# pyboard_arcobaleno.net
KiCad netlist of a schematic drawn in EAGLE
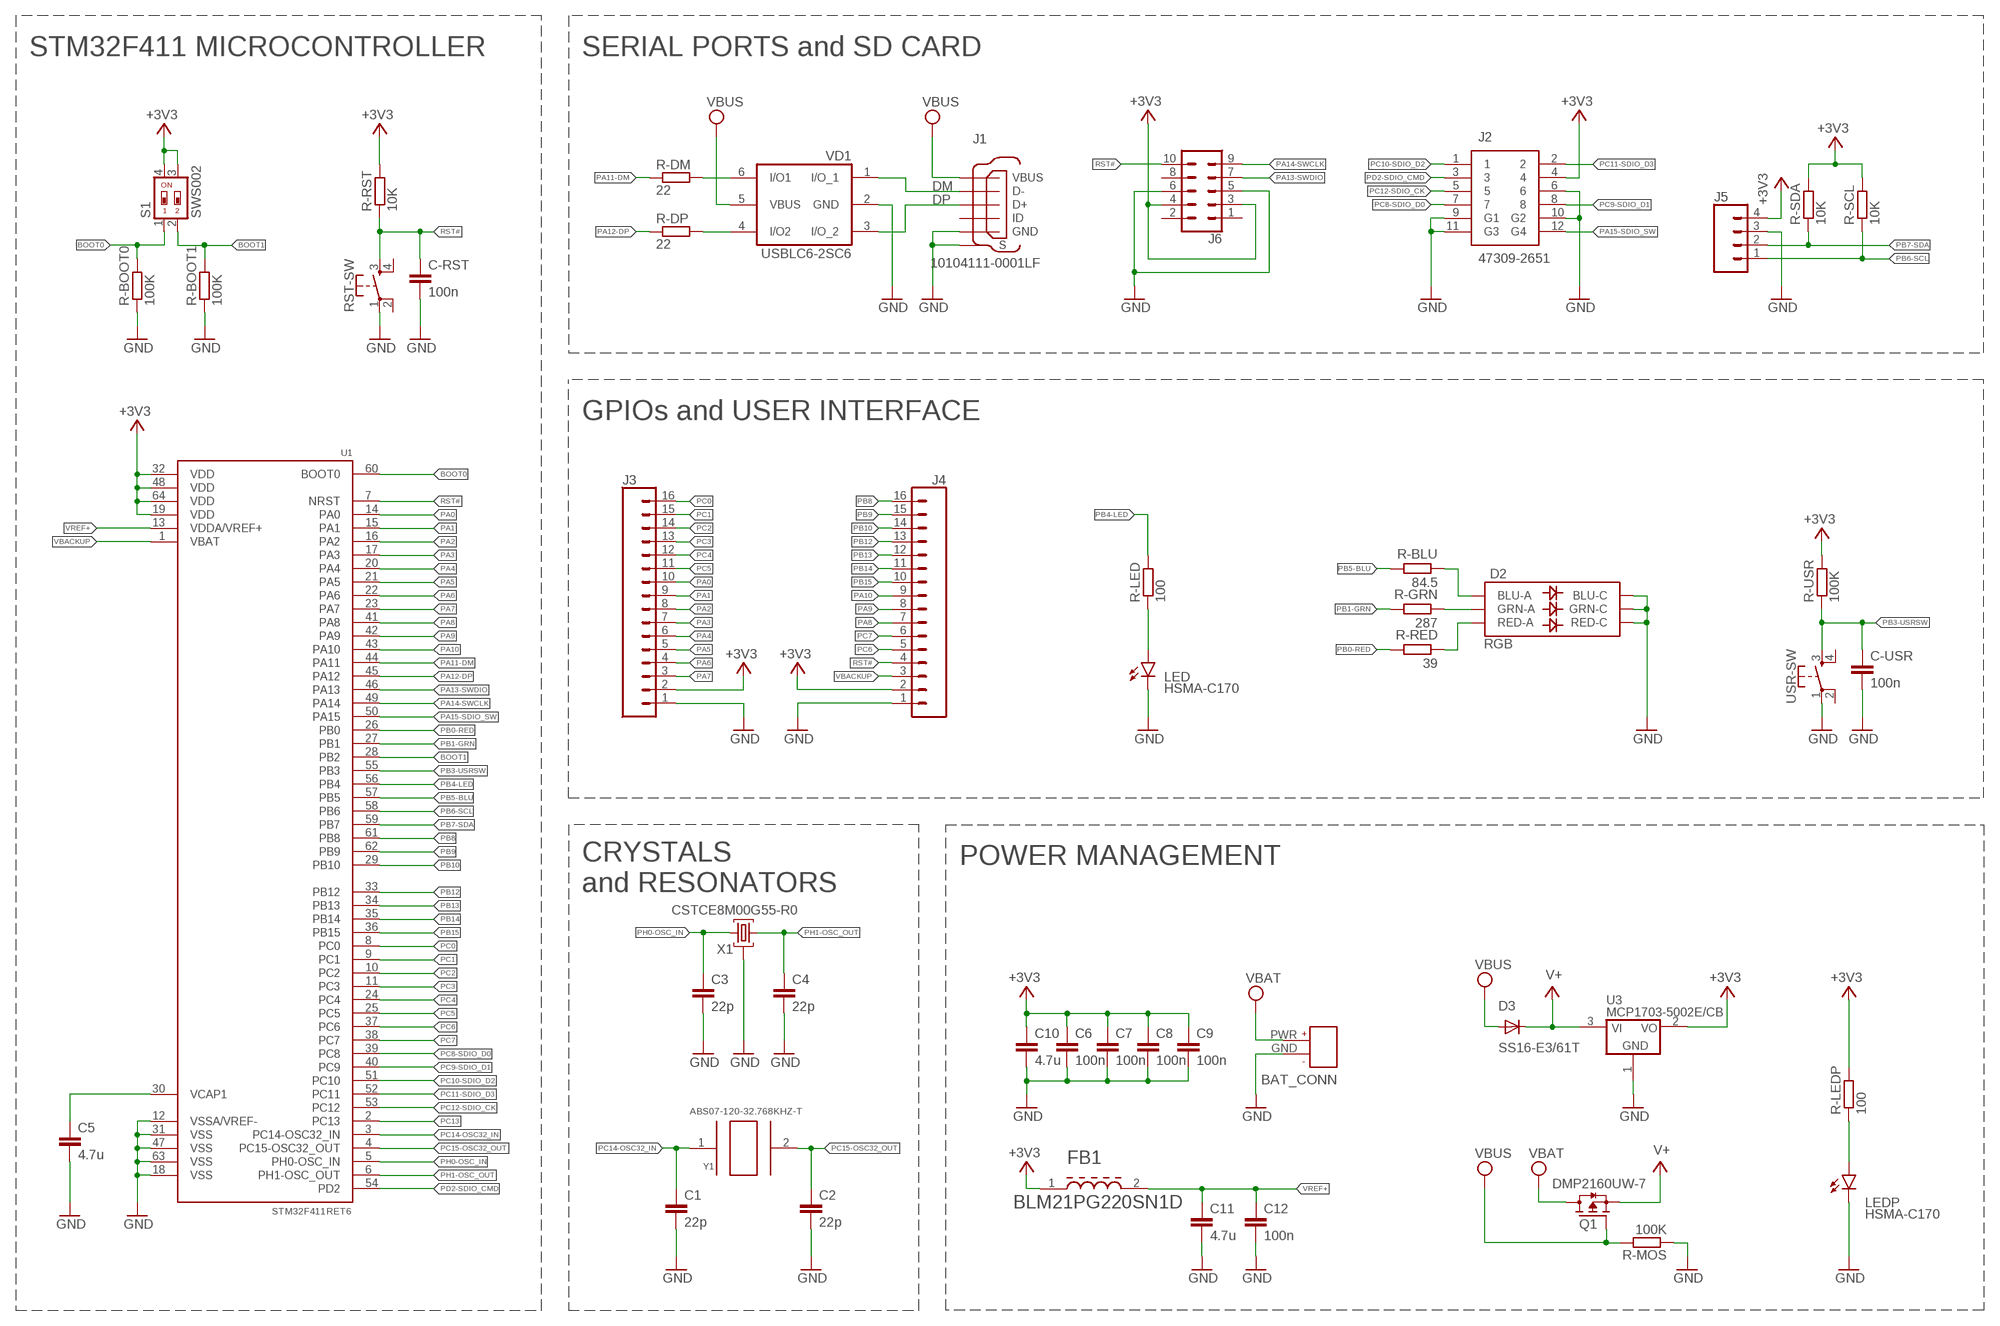
[diagram p0: schematic, sheet 1]

(export (version "E")
  (design (tool "Eeschema 10.0.6"))
  (components
    (comp (ref "BAT_CONN")
      (value "JST_PH_2PIN")
      (footprint "eagle-import:JST_PH_2PIN")
      (libsource (lib "eagle-import") (part "JST_PH_2PIN"))
    )
    (comp (ref "C-RST")
      (value "100n")
      (footprint "eagle-import:C0603")
      (libsource (lib "eagle-import") (part "C-EUC0603"))
    )
    (comp (ref "C-USR")
      (value "100n")
      (footprint "eagle-import:C0603")
      (libsource (lib "eagle-import") (part "C-EUC0603"))
    )
    (comp (ref "C1")
      (value "22p")
      (footprint "eagle-import:C0603")
      (libsource (lib "eagle-import") (part "C-EUC0603"))
    )
    (comp (ref "C2")
      (value "22p")
      (footprint "eagle-import:C0603")
      (libsource (lib "eagle-import") (part "C-EUC0603"))
    )
    (comp (ref "C3")
      (value "22p")
      (footprint "eagle-import:C0603")
      (libsource (lib "eagle-import") (part "C-EUC0603"))
    )
    (comp (ref "C4")
      (value "22p")
      (footprint "eagle-import:C0603")
      (libsource (lib "eagle-import") (part "C-EUC0603"))
    )
    (comp (ref "C5")
      (value "4.7u")
      (footprint "eagle-import:C1608")
      (libsource (lib "eagle-import") (part "rcl_334_C-EUC1608"))
    )
    (comp (ref "C6")
      (value "100n")
      (footprint "eagle-import:C0603")
      (libsource (lib "eagle-import") (part "C-EUC0603"))
    )
    (comp (ref "C7")
      (value "100n")
      (footprint "eagle-import:C0603")
      (libsource (lib "eagle-import") (part "C-EUC0603"))
    )
    (comp (ref "C8")
      (value "100n")
      (footprint "eagle-import:C0603")
      (libsource (lib "eagle-import") (part "C-EUC0603"))
    )
    (comp (ref "C9")
      (value "100n")
      (footprint "eagle-import:C0603")
      (libsource (lib "eagle-import") (part "C-EUC0603"))
    )
    (comp (ref "C10")
      (value "4.7u")
      (footprint "eagle-import:C1608")
      (libsource (lib "eagle-import") (part "rcl_334_C-EUC1608"))
    )
    (comp (ref "C11")
      (value "4.7u")
      (footprint "eagle-import:C1608")
      (libsource (lib "eagle-import") (part "rcl_334_C-EUC1608"))
    )
    (comp (ref "C12")
      (value "100n")
      (footprint "eagle-import:C0603")
      (libsource (lib "eagle-import") (part "C-EUC0603"))
    )
    (comp (ref "D2")
      (value "RGB")
      (footprint "eagle-import:PLCC-6-LED")
      (libsource (lib "eagle-import") (part "LED-RGBPLCC-6"))
    )
    (comp (ref "D3")
      (value "SS16-E3/61T")
      (footprint "eagle-import:DO214AA")
      (libsource (lib "eagle-import") (part "DIODE-DO214AA"))
    )
    (comp (ref "FB1")
      (value "MURATA_BLM21PG220SN1DMURATA_BLM21PG220SN1D_0_0")
      (footprint "eagle-import:MURATA_BLM21PG220SN1D_0")
      (fields (field (name "MF") "Murata") (field (name "MPN") "BLM21PG220SN1D"))
      (libsource (lib "eagle-import") (part "MURATA_BLM21PG220SN1DMURATA_BLM21PG220SN1D_0_0"))
    )
    (comp (ref "J1")
      (value "10104111-0001LF")
      (footprint "eagle-import:FRAMATOME_10104111-0001LF")
      (fields (field (name "MF") "Amphenol ICC"))
      (libsource (lib "eagle-import") (part "10104111-0001LF"))
    )
    (comp (ref "J2")
      (value "47309-2651")
      (footprint "eagle-import:47309-2651")
      (fields (field (name "MOUSER_PART_NUMBER") "538-47309-2651") (field (name "RS_PART_NUMBER") "7025485P"))
      (libsource (lib "eagle-import") (part "47309-2651"))
    )
    (comp (ref "J3")
      (value "CONN_16")
      (footprint "eagle-import:1X16")
      (libsource (lib "eagle-import") (part "CONN_16"))
    )
    (comp (ref "J4")
      (value "CONN_16")
      (footprint "eagle-import:1X16")
      (libsource (lib "eagle-import") (part "CONN_16"))
    )
    (comp (ref "J5")
      (value "CONN_04")
      (footprint "eagle-import:1X04")
      (libsource (lib "eagle-import") (part "CONN_04"))
    )
    (comp (ref "J6")
      (value "CONN_05X2PTH")
      (footprint "eagle-import:2X5")
      (libsource (lib "eagle-import") (part "CONN_05X2PTH"))
    )
    (comp (ref "LED")
      (value "HSMA-C170")
      (footprint "eagle-import:CHIPLED_0805")
      (libsource (lib "eagle-import") (part "LEDCHIPLED_0805"))
    )
    (comp (ref "LEDP")
      (value "HSMA-C170")
      (footprint "eagle-import:CHIPLED_0805")
      (libsource (lib "eagle-import") (part "LEDCHIPLED_0805"))
    )
    (comp (ref "Q1")
      (value "DMP2160UW-7")
      (footprint "eagle-import:SOT65P210X110-3N")
      (fields (field (name "DIGI-KEY_PART_NUMBER") "DMP2160UWDICT-ND") (field (name "MF") "Diodes Inc."))
      (libsource (lib "eagle-import") (part "DMP2160UW-7"))
    )
    (comp (ref "R-BLU")
      (value "84.5")
      (footprint "eagle-import:R0603")
      (libsource (lib "eagle-import") (part "R-EU_R0603"))
    )
    (comp (ref "R-BOOT0")
      (value "100K")
      (footprint "eagle-import:R0603")
      (libsource (lib "eagle-import") (part "R-EU_R0603"))
    )
    (comp (ref "R-BOOT1")
      (value "100K")
      (footprint "eagle-import:R0603")
      (libsource (lib "eagle-import") (part "R-EU_R0603"))
    )
    (comp (ref "R-DM")
      (value "22")
      (footprint "eagle-import:R0603")
      (libsource (lib "eagle-import") (part "R-EU_R0603"))
    )
    (comp (ref "R-DP")
      (value "22")
      (footprint "eagle-import:R0603")
      (libsource (lib "eagle-import") (part "R-EU_R0603"))
    )
    (comp (ref "R-GRN")
      (value "287")
      (footprint "eagle-import:R0603")
      (libsource (lib "eagle-import") (part "R-EU_R0603"))
    )
    (comp (ref "R-LED")
      (value "100")
      (footprint "eagle-import:R0603")
      (libsource (lib "eagle-import") (part "R-EU_R0603"))
    )
    (comp (ref "R-LEDP")
      (value "100")
      (footprint "eagle-import:R0603")
      (libsource (lib "eagle-import") (part "R-EU_R0603"))
    )
    (comp (ref "R-MOS")
      (value "100K")
      (footprint "eagle-import:R0603")
      (libsource (lib "eagle-import") (part "R-EU_R0603"))
    )
    (comp (ref "R-RED")
      (value "39")
      (footprint "eagle-import:R0603")
      (libsource (lib "eagle-import") (part "R-EU_R0603"))
    )
    (comp (ref "R-RST")
      (value "10K")
      (footprint "eagle-import:R0603")
      (libsource (lib "eagle-import") (part "R-EU_R0603"))
    )
    (comp (ref "R-SCL")
      (value "10K")
      (footprint "eagle-import:R0603")
      (libsource (lib "eagle-import") (part "R-EU_R0603"))
    )
    (comp (ref "R-SDA")
      (value "10K")
      (footprint "eagle-import:R0603")
      (libsource (lib "eagle-import") (part "R-EU_R0603"))
    )
    (comp (ref "R-USR")
      (value "100K")
      (footprint "eagle-import:R0603")
      (libsource (lib "eagle-import") (part "R-EU_R0603"))
    )
    (comp (ref "RST-SW")
      (value "MOMENTARY-SWITCH-SPST-2-SMD-5.2MM")
      (footprint "eagle-import:TACTILE_SWITCH_SMD_5.2MM")
      (libsource (lib "eagle-import") (part "MOMENTARY-SWITCH-SPST-2-SMD-5.2MM"))
    )
    (comp (ref "S1")
      (value "SWS002")
      (footprint "eagle-import:SMS-002")
      (libsource (lib "eagle-import") (part "SWS002"))
    )
    (comp (ref "U1")
      (value "STM32F411RET6")
      (footprint "eagle-import:QFP50P1200X1200X160-64N")
      (fields (field (name "MF") "STMicroelectronics"))
      (libsource (lib "eagle-import") (part "STM32F411RET6"))
    )
    (comp (ref "U3")
      (value "MCP1703-5002E/CB")
      (footprint "eagle-import:SOT23A_MICROCHIP_CB")
      (libsource (lib "eagle-import") (part "MCP170302E/CB-50"))
    )
    (comp (ref "USR-SW")
      (value "MOMENTARY-SWITCH-SPST-2-SMD-5.2MM")
      (footprint "eagle-import:TACTILE_SWITCH_SMD_5.2MM")
      (libsource (lib "eagle-import") (part "MOMENTARY-SWITCH-SPST-2-SMD-5.2MM"))
    )
    (comp (ref "VD1")
      (value "USBLC6-2SC6")
      (footprint "eagle-import:SOT-23-6L")
      (libsource (lib "eagle-import") (part "USBLC6-2SC6"))
    )
    (comp (ref "X1")
      (value "CSTCE8M00G55-R0")
      (footprint "eagle-import:CSTCE8M00G55-R0")
      (fields
        (field (name "DIGIKEY_PART_NUMBER") "490-1195-2-ND")
        (field (name "MANUFACTURER") "Murata Electronics North America")
        (field (name "CREATED_BY") "PCBLayout.com")
      )
      (libsource (lib "eagle-import") (part "CSTCE8M00G55-R0"))
    )
    (comp (ref "Y1")
      (value "ABS07-120-32.768KHZ-T")
      (footprint "eagle-import:XTAL_ABS07-120-32.768KHZ-T")
      (fields (field (name "DIGI-KEY_PART_NUMBER") "535-11937-1-ND") (field (name "MF") "Abracon"))
      (libsource (lib "eagle-import") (part "ABS07-120-32.768KHZ-T"))
    )
  )
  (nets
    (net (code "1") (name "+3V3") (class "Default")
      (node (ref "C10") (pin "1") (pinfunction "1_1") (pintype "passive"))
      (node (ref "C6") (pin "1") (pinfunction "1_1") (pintype "passive"))
      (node (ref "C7") (pin "1") (pinfunction "1_1") (pintype "passive"))
      (node (ref "C8") (pin "1") (pinfunction "1_1") (pintype "passive"))
      (node (ref "C9") (pin "1") (pinfunction "1_1") (pintype "passive"))
      (node (ref "FB1") (pin "1") (pinfunction "1_1") (pintype "passive"))
      (node (ref "J2") (pin "4") (pinfunction "4_4") (pintype "bidirectional"))
      (node (ref "J3") (pin "2") (pinfunction "2_2") (pintype "passive"))
      (node (ref "J4") (pin "2") (pinfunction "2_2") (pintype "passive"))
      (node (ref "J5") (pin "4") (pinfunction "4_4") (pintype "passive"))
      (node (ref "J6") (pin "3") (pinfunction "3_3") (pintype "passive"))
      (node (ref "J6") (pin "4") (pinfunction "4_4") (pintype "passive"))
      (node (ref "R-LEDP") (pin "2") (pinfunction "2_2") (pintype "passive"))
      (node (ref "R-RST") (pin "2") (pinfunction "2_2") (pintype "passive"))
      (node (ref "R-SCL") (pin "2") (pinfunction "2_2") (pintype "passive"))
      (node (ref "R-SDA") (pin "2") (pinfunction "2_2") (pintype "passive"))
      (node (ref "R-USR") (pin "2") (pinfunction "2_2") (pintype "passive"))
      (node (ref "S1") (pin "3") (pinfunction "3_3") (pintype "passive"))
      (node (ref "S1") (pin "4") (pinfunction "4_4") (pintype "passive"))
      (node (ref "U1") (pin "19") (pinfunction "VDD_19") (pintype "power_in"))
      (node (ref "U1") (pin "32") (pinfunction "VDD_32") (pintype "power_in"))
      (node (ref "U1") (pin "48") (pinfunction "VDD_48") (pintype "power_in"))
      (node (ref "U1") (pin "64") (pinfunction "VDD_64") (pintype "power_in"))
      (node (ref "U3") (pin "2") (pinfunction "VO_2") (pintype "passive"))
    )
    (net (code "2") (name "/DM") (class "Default")
      (node (ref "J1") (pin "2") (pinfunction "D-_2") (pintype "passive"))
      (node (ref "VD1") (pin "1") (pinfunction "I/O_1_1") (pintype "bidirectional"))
    )
    (net (code "3") (name "/DP") (class "Default")
      (node (ref "J1") (pin "3") (pinfunction "D+_3") (pintype "passive"))
      (node (ref "VD1") (pin "3") (pinfunction "I/O_2_3") (pintype "bidirectional"))
    )
    (net (code "4") (name "BOOT0") (class "Default")
      (node (ref "R-BOOT0") (pin "2") (pinfunction "2_2") (pintype "passive"))
      (node (ref "S1") (pin "1") (pinfunction "1_1") (pintype "passive"))
      (node (ref "U1") (pin "60") (pinfunction "BOOT0_60") (pintype "input"))
    )
    (net (code "5") (name "BOOT1") (class "Default")
      (node (ref "R-BOOT1") (pin "2") (pinfunction "2_2") (pintype "passive"))
      (node (ref "S1") (pin "2") (pinfunction "2_2") (pintype "passive"))
      (node (ref "U1") (pin "28") (pinfunction "PB2_28") (pintype "bidirectional"))
    )
    (net (code "6") (name "GND") (class "Default")
      (node (ref "BAT_CONN") (pin "GND") (pinfunction "GND_GND") (pintype "power_in"))
      (node (ref "C-RST") (pin "2") (pinfunction "2_2") (pintype "passive"))
      (node (ref "C-USR") (pin "2") (pinfunction "2_2") (pintype "passive"))
      (node (ref "C1") (pin "2") (pinfunction "2_2") (pintype "passive"))
      (node (ref "C10") (pin "2") (pinfunction "2_2") (pintype "passive"))
      (node (ref "C11") (pin "2") (pinfunction "2_2") (pintype "passive"))
      (node (ref "C12") (pin "2") (pinfunction "2_2") (pintype "passive"))
      (node (ref "C2") (pin "2") (pinfunction "2_2") (pintype "passive"))
      (node (ref "C3") (pin "2") (pinfunction "2_2") (pintype "passive"))
      (node (ref "C4") (pin "2") (pinfunction "2_2") (pintype "passive"))
      (node (ref "C5") (pin "2") (pinfunction "2_2") (pintype "passive"))
      (node (ref "C6") (pin "2") (pinfunction "2_2") (pintype "passive"))
      (node (ref "C7") (pin "2") (pinfunction "2_2") (pintype "passive"))
      (node (ref "C8") (pin "2") (pinfunction "2_2") (pintype "passive"))
      (node (ref "C9") (pin "2") (pinfunction "2_2") (pintype "passive"))
      (node (ref "D2") (pin "CB") (pinfunction "BLU-C_CB") (pintype "bidirectional"))
      (node (ref "D2") (pin "CG") (pinfunction "GRN-C_CG") (pintype "bidirectional"))
      (node (ref "D2") (pin "CR") (pinfunction "RED-C_CR") (pintype "bidirectional"))
      (node (ref "J1") (pin "5") (pinfunction "GND_5") (pintype "power_in"))
      (node (ref "J1") (pin "6") (pinfunction "S_6") (pintype "power_in"))
      (node (ref "J1") (pin "7") (pinfunction "S_7") (pintype "power_in"))
      (node (ref "J1") (pin "8") (pinfunction "S_8") (pintype "power_in"))
      (node (ref "J1") (pin "9") (pinfunction "S_9") (pintype "power_in"))
      (node (ref "J2") (pin "10") (pinfunction "G2_10") (pintype "bidirectional"))
      (node (ref "J2") (pin "11") (pinfunction "G3_11") (pintype "bidirectional"))
      (node (ref "J2") (pin "6") (pinfunction "6_6") (pintype "bidirectional"))
      (node (ref "J2") (pin "9") (pinfunction "G1_9") (pintype "bidirectional"))
      (node (ref "J3") (pin "1") (pinfunction "1_1") (pintype "passive"))
      (node (ref "J4") (pin "1") (pinfunction "1_1") (pintype "passive"))
      (node (ref "J5") (pin "3") (pinfunction "3_3") (pintype "passive"))
      (node (ref "J6") (pin "5") (pinfunction "5_5") (pintype "passive"))
      (node (ref "J6") (pin "6") (pinfunction "6_6") (pintype "passive"))
      (node (ref "LED") (pin "C") (pinfunction "C_C") (pintype "passive"))
      (node (ref "LEDP") (pin "C") (pinfunction "C_C") (pintype "passive"))
      (node (ref "R-BOOT0") (pin "1") (pinfunction "1_1") (pintype "passive"))
      (node (ref "R-BOOT1") (pin "1") (pinfunction "1_1") (pintype "passive"))
      (node (ref "R-MOS") (pin "1") (pinfunction "1_1") (pintype "passive"))
      (node (ref "RST-SW") (pin "1") (pinfunction "1_1") (pintype "passive"))
      (node (ref "U1") (pin "12") (pinfunction "VSSA/VREF-_12") (pintype "power_in"))
      (node (ref "U1") (pin "18") (pinfunction "VSS_18") (pintype "power_in"))
      (node (ref "U1") (pin "31") (pinfunction "VSS_31") (pintype "power_in"))
      (node (ref "U1") (pin "47") (pinfunction "VSS_47") (pintype "power_in"))
      (node (ref "U1") (pin "63") (pinfunction "VSS_63") (pintype "power_in"))
      (node (ref "U3") (pin "1") (pinfunction "GND_1") (pintype "power_in"))
      (node (ref "USR-SW") (pin "1") (pinfunction "1_1") (pintype "passive"))
      (node (ref "VD1") (pin "2") (pinfunction "GND_2") (pintype "bidirectional"))
      (node (ref "X1") (pin "2") (pinfunction "GND_2") (pintype "passive"))
    )
    (net (code "7") (name "Net-(D2-BLU-A)") (class "Default")
      (node (ref "D2") (pin "AB") (pinfunction "BLU-A_AB") (pintype "bidirectional"))
      (node (ref "R-BLU") (pin "1") (pinfunction "1_1") (pintype "passive"))
    )
    (net (code "8") (name "Net-(D2-GRN-A)") (class "Default")
      (node (ref "D2") (pin "AG") (pinfunction "GRN-A_AG") (pintype "bidirectional"))
      (node (ref "R-GRN") (pin "1") (pinfunction "1_1") (pintype "passive"))
    )
    (net (code "9") (name "Net-(D2-RED-A)") (class "Default")
      (node (ref "D2") (pin "AR") (pinfunction "RED-A_AR") (pintype "bidirectional"))
      (node (ref "R-RED") (pin "1") (pinfunction "1_1") (pintype "passive"))
    )
    (net (code "10") (name "Net-(LED-PadA)") (class "Default")
      (node (ref "LED") (pin "A") (pinfunction "A_A") (pintype "passive"))
      (node (ref "R-LED") (pin "1") (pinfunction "1_1") (pintype "passive"))
    )
    (net (code "11") (name "Net-(LEDP-PadA)") (class "Default")
      (node (ref "LEDP") (pin "A") (pinfunction "A_A") (pintype "passive"))
      (node (ref "R-LEDP") (pin "1") (pinfunction "1_1") (pintype "passive"))
    )
    (net (code "12") (name "Net-(U1-VCAP1)") (class "Default")
      (node (ref "C5") (pin "1") (pinfunction "1_1") (pintype "passive"))
      (node (ref "U1") (pin "30") (pinfunction "VCAP1_30") (pintype "passive"))
    )
    (net (code "13") (name "Net-(VD1-I{slash}O1)") (class "Default")
      (node (ref "R-DM") (pin "2") (pinfunction "2_2") (pintype "passive"))
      (node (ref "VD1") (pin "6") (pinfunction "I/O1_6") (pintype "bidirectional"))
    )
    (net (code "14") (name "Net-(VD1-I{slash}O2)") (class "Default")
      (node (ref "R-DP") (pin "2") (pinfunction "2_2") (pintype "passive"))
      (node (ref "VD1") (pin "4") (pinfunction "I/O2_4") (pintype "bidirectional"))
    )
    (net (code "15") (name "PA0") (class "Default")
      (node (ref "J3") (pin "10") (pinfunction "10_10") (pintype "passive"))
      (node (ref "U1") (pin "14") (pinfunction "PA0_14") (pintype "bidirectional"))
    )
    (net (code "16") (name "PA1") (class "Default")
      (node (ref "J3") (pin "9") (pinfunction "9_9") (pintype "passive"))
      (node (ref "U1") (pin "15") (pinfunction "PA1_15") (pintype "bidirectional"))
    )
    (net (code "17") (name "PA2") (class "Default")
      (node (ref "J3") (pin "8") (pinfunction "8_8") (pintype "passive"))
      (node (ref "U1") (pin "16") (pinfunction "PA2_16") (pintype "bidirectional"))
    )
    (net (code "18") (name "PA3") (class "Default")
      (node (ref "J3") (pin "7") (pinfunction "7_7") (pintype "passive"))
      (node (ref "U1") (pin "17") (pinfunction "PA3_17") (pintype "bidirectional"))
    )
    (net (code "19") (name "PA4") (class "Default")
      (node (ref "J3") (pin "6") (pinfunction "6_6") (pintype "passive"))
      (node (ref "U1") (pin "20") (pinfunction "PA4_20") (pintype "bidirectional"))
    )
    (net (code "20") (name "PA5") (class "Default")
      (node (ref "J3") (pin "5") (pinfunction "5_5") (pintype "passive"))
      (node (ref "U1") (pin "21") (pinfunction "PA5_21") (pintype "bidirectional"))
    )
    (net (code "21") (name "PA6") (class "Default")
      (node (ref "J3") (pin "4") (pinfunction "4_4") (pintype "passive"))
      (node (ref "U1") (pin "22") (pinfunction "PA6_22") (pintype "bidirectional"))
    )
    (net (code "22") (name "PA7") (class "Default")
      (node (ref "J3") (pin "3") (pinfunction "3_3") (pintype "passive"))
      (node (ref "U1") (pin "23") (pinfunction "PA7_23") (pintype "bidirectional"))
    )
    (net (code "23") (name "PA8") (class "Default")
      (node (ref "J4") (pin "7") (pinfunction "7_7") (pintype "passive"))
      (node (ref "U1") (pin "41") (pinfunction "PA8_41") (pintype "bidirectional"))
    )
    (net (code "24") (name "PA9") (class "Default")
      (node (ref "J4") (pin "8") (pinfunction "8_8") (pintype "passive"))
      (node (ref "U1") (pin "42") (pinfunction "PA9_42") (pintype "bidirectional"))
    )
    (net (code "25") (name "PA10") (class "Default")
      (node (ref "J4") (pin "9") (pinfunction "9_9") (pintype "passive"))
      (node (ref "U1") (pin "43") (pinfunction "PA10_43") (pintype "bidirectional"))
    )
    (net (code "26") (name "PA11-DM") (class "Default")
      (node (ref "R-DM") (pin "1") (pinfunction "1_1") (pintype "passive"))
      (node (ref "U1") (pin "44") (pinfunction "PA11_44") (pintype "bidirectional"))
    )
    (net (code "27") (name "PA12-DP") (class "Default")
      (node (ref "R-DP") (pin "1") (pinfunction "1_1") (pintype "passive"))
      (node (ref "U1") (pin "45") (pinfunction "PA12_45") (pintype "bidirectional"))
    )
    (net (code "28") (name "PA13-SWDIO") (class "Default")
      (node (ref "J6") (pin "7") (pinfunction "7_7") (pintype "passive"))
      (node (ref "U1") (pin "46") (pinfunction "PA13_46") (pintype "bidirectional"))
    )
    (net (code "29") (name "PA14-SWCLK") (class "Default")
      (node (ref "J6") (pin "9") (pinfunction "9_9") (pintype "passive"))
      (node (ref "U1") (pin "49") (pinfunction "PA14_49") (pintype "bidirectional"))
    )
    (net (code "30") (name "PA15-SDIO_SW") (class "Default")
      (node (ref "J2") (pin "12") (pinfunction "G4_12") (pintype "bidirectional"))
      (node (ref "U1") (pin "50") (pinfunction "PA15_50") (pintype "bidirectional"))
    )
    (net (code "31") (name "PB0-RED") (class "Default")
      (node (ref "R-RED") (pin "2") (pinfunction "2_2") (pintype "passive"))
      (node (ref "U1") (pin "26") (pinfunction "PB0_26") (pintype "bidirectional"))
    )
    (net (code "32") (name "PB1-GRN") (class "Default")
      (node (ref "R-GRN") (pin "2") (pinfunction "2_2") (pintype "passive"))
      (node (ref "U1") (pin "27") (pinfunction "PB1_27") (pintype "bidirectional"))
    )
    (net (code "33") (name "PB3-USRSW") (class "Default")
      (node (ref "C-USR") (pin "1") (pinfunction "1_1") (pintype "passive"))
      (node (ref "R-USR") (pin "1") (pinfunction "1_1") (pintype "passive"))
      (node (ref "U1") (pin "55") (pinfunction "PB3_55") (pintype "bidirectional"))
      (node (ref "USR-SW") (pin "3") (pinfunction "3_3") (pintype "passive"))
    )
    (net (code "34") (name "PB4-LED") (class "Default")
      (node (ref "R-LED") (pin "2") (pinfunction "2_2") (pintype "passive"))
      (node (ref "U1") (pin "56") (pinfunction "PB4_56") (pintype "bidirectional"))
    )
    (net (code "35") (name "PB5-BLU") (class "Default")
      (node (ref "R-BLU") (pin "2") (pinfunction "2_2") (pintype "passive"))
      (node (ref "U1") (pin "57") (pinfunction "PB5_57") (pintype "bidirectional"))
    )
    (net (code "36") (name "PB6-SCL") (class "Default")
      (node (ref "J5") (pin "1") (pinfunction "1_1") (pintype "passive"))
      (node (ref "R-SCL") (pin "1") (pinfunction "1_1") (pintype "passive"))
      (node (ref "U1") (pin "58") (pinfunction "PB6_58") (pintype "bidirectional"))
    )
    (net (code "37") (name "PB7-SDA") (class "Default")
      (node (ref "J5") (pin "2") (pinfunction "2_2") (pintype "passive"))
      (node (ref "R-SDA") (pin "1") (pinfunction "1_1") (pintype "passive"))
      (node (ref "U1") (pin "59") (pinfunction "PB7_59") (pintype "bidirectional"))
    )
    (net (code "38") (name "PB8") (class "Default")
      (node (ref "J4") (pin "16") (pinfunction "16_16") (pintype "passive"))
      (node (ref "U1") (pin "61") (pinfunction "PB8_61") (pintype "bidirectional"))
    )
    (net (code "39") (name "PB9") (class "Default")
      (node (ref "J4") (pin "15") (pinfunction "15_15") (pintype "passive"))
      (node (ref "U1") (pin "62") (pinfunction "PB9_62") (pintype "bidirectional"))
    )
    (net (code "40") (name "PB10") (class "Default")
      (node (ref "J4") (pin "14") (pinfunction "14_14") (pintype "passive"))
      (node (ref "U1") (pin "29") (pinfunction "PB10_29") (pintype "bidirectional"))
    )
    (net (code "41") (name "PB12") (class "Default")
      (node (ref "J4") (pin "13") (pinfunction "13_13") (pintype "passive"))
      (node (ref "U1") (pin "33") (pinfunction "PB12_33") (pintype "bidirectional"))
    )
    (net (code "42") (name "PB13") (class "Default")
      (node (ref "J4") (pin "12") (pinfunction "12_12") (pintype "passive"))
      (node (ref "U1") (pin "34") (pinfunction "PB13_34") (pintype "bidirectional"))
    )
    (net (code "43") (name "PB14") (class "Default")
      (node (ref "J4") (pin "11") (pinfunction "11_11") (pintype "passive"))
      (node (ref "U1") (pin "35") (pinfunction "PB14_35") (pintype "bidirectional"))
    )
    (net (code "44") (name "PB15") (class "Default")
      (node (ref "J4") (pin "10") (pinfunction "10_10") (pintype "passive"))
      (node (ref "U1") (pin "36") (pinfunction "PB15_36") (pintype "bidirectional"))
    )
    (net (code "45") (name "PC0") (class "Default")
      (node (ref "J3") (pin "16") (pinfunction "16_16") (pintype "passive"))
      (node (ref "U1") (pin "8") (pinfunction "PC0_8") (pintype "bidirectional"))
    )
    (net (code "46") (name "PC1") (class "Default")
      (node (ref "J3") (pin "15") (pinfunction "15_15") (pintype "passive"))
      (node (ref "U1") (pin "9") (pinfunction "PC1_9") (pintype "bidirectional"))
    )
    (net (code "47") (name "PC2") (class "Default")
      (node (ref "J3") (pin "14") (pinfunction "14_14") (pintype "passive"))
      (node (ref "U1") (pin "10") (pinfunction "PC2_10") (pintype "bidirectional"))
    )
    (net (code "48") (name "PC3") (class "Default")
      (node (ref "J3") (pin "13") (pinfunction "13_13") (pintype "passive"))
      (node (ref "U1") (pin "11") (pinfunction "PC3_11") (pintype "bidirectional"))
    )
    (net (code "49") (name "PC4") (class "Default")
      (node (ref "J3") (pin "12") (pinfunction "12_12") (pintype "passive"))
      (node (ref "U1") (pin "24") (pinfunction "PC4_24") (pintype "bidirectional"))
    )
    (net (code "50") (name "PC5") (class "Default")
      (node (ref "J3") (pin "11") (pinfunction "11_11") (pintype "passive"))
      (node (ref "U1") (pin "25") (pinfunction "PC5_25") (pintype "bidirectional"))
    )
    (net (code "51") (name "PC6") (class "Default")
      (node (ref "J4") (pin "5") (pinfunction "5_5") (pintype "passive"))
      (node (ref "U1") (pin "37") (pinfunction "PC6_37") (pintype "bidirectional"))
    )
    (net (code "52") (name "PC7") (class "Default")
      (node (ref "J4") (pin "6") (pinfunction "6_6") (pintype "passive"))
      (node (ref "U1") (pin "38") (pinfunction "PC7_38") (pintype "bidirectional"))
    )
    (net (code "53") (name "PC8-SDIO_D0") (class "Default")
      (node (ref "J2") (pin "7") (pinfunction "7_7") (pintype "bidirectional"))
      (node (ref "U1") (pin "39") (pinfunction "PC8_39") (pintype "bidirectional"))
    )
    (net (code "54") (name "PC9-SDIO_D1") (class "Default")
      (node (ref "J2") (pin "8") (pinfunction "8_8") (pintype "bidirectional"))
      (node (ref "U1") (pin "40") (pinfunction "PC9_40") (pintype "bidirectional"))
    )
    (net (code "55") (name "PC10-SDIO_D2") (class "Default")
      (node (ref "J2") (pin "1") (pinfunction "1_1") (pintype "bidirectional"))
      (node (ref "U1") (pin "51") (pinfunction "PC10_51") (pintype "bidirectional"))
    )
    (net (code "56") (name "PC11-SDIO_D3") (class "Default")
      (node (ref "J2") (pin "2") (pinfunction "2_2") (pintype "bidirectional"))
      (node (ref "U1") (pin "52") (pinfunction "PC11_52") (pintype "bidirectional"))
    )
    (net (code "57") (name "PC12-SDIO_CK") (class "Default")
      (node (ref "J2") (pin "5") (pinfunction "5_5") (pintype "bidirectional"))
      (node (ref "U1") (pin "53") (pinfunction "PC12_53") (pintype "bidirectional"))
    )
    (net (code "58") (name "PC13") (class "Default")
      (node (ref "U1") (pin "2") (pinfunction "PC13_2") (pintype "bidirectional"))
    )
    (net (code "59") (name "PC14-OSC32_IN") (class "Default")
      (node (ref "C1") (pin "1") (pinfunction "1_1") (pintype "passive"))
      (node (ref "U1") (pin "3") (pinfunction "PC14-OSC32_IN_3") (pintype "bidirectional"))
      (node (ref "Y1") (pin "1") (pinfunction "1_1") (pintype "passive"))
    )
    (net (code "60") (name "PC15-OSC32_OUT") (class "Default")
      (node (ref "C2") (pin "1") (pinfunction "1_1") (pintype "passive"))
      (node (ref "U1") (pin "4") (pinfunction "PC15-OSC32_OUT_4") (pintype "bidirectional"))
      (node (ref "Y1") (pin "2") (pinfunction "2_2") (pintype "passive"))
    )
    (net (code "61") (name "PD2-SDIO_CMD") (class "Default")
      (node (ref "J2") (pin "3") (pinfunction "3_3") (pintype "bidirectional"))
      (node (ref "U1") (pin "54") (pinfunction "PD2_54") (pintype "bidirectional"))
    )
    (net (code "62") (name "PH0-OSC_IN") (class "Default")
      (node (ref "C3") (pin "1") (pinfunction "1_1") (pintype "passive"))
      (node (ref "U1") (pin "5") (pinfunction "PH0-OSC_IN_5") (pintype "bidirectional"))
      (node (ref "X1") (pin "1") (pinfunction "INPUT_1") (pintype "passive"))
    )
    (net (code "63") (name "PH1-OSC_OUT") (class "Default")
      (node (ref "C4") (pin "1") (pinfunction "1_1") (pintype "passive"))
      (node (ref "U1") (pin "6") (pinfunction "PH1-OSC_OUT_6") (pintype "bidirectional"))
      (node (ref "X1") (pin "3") (pinfunction "OUTPUT_3") (pintype "passive"))
    )
    (net (code "64") (name "RST#") (class "Default")
      (node (ref "C-RST") (pin "1") (pinfunction "1_1") (pintype "passive"))
      (node (ref "J4") (pin "4") (pinfunction "4_4") (pintype "passive"))
      (node (ref "J6") (pin "10") (pinfunction "10_10") (pintype "passive"))
      (node (ref "R-RST") (pin "1") (pinfunction "1_1") (pintype "passive"))
      (node (ref "RST-SW") (pin "3") (pinfunction "3_3") (pintype "passive"))
      (node (ref "U1") (pin "7") (pinfunction "NRST_7") (pintype "bidirectional"))
    )
    (net (code "65") (name "V+") (class "Default")
      (node (ref "D3") (pin "C") (pinfunction "C_C") (pintype "passive"))
      (node (ref "Q1") (pin "2") (pinfunction "S_2") (pintype "passive"))
      (node (ref "U3") (pin "3") (pinfunction "VI_3") (pintype "power_in"))
    )
    (net (code "66") (name "VBACKUP") (class "Default")
      (node (ref "J4") (pin "3") (pinfunction "3_3") (pintype "passive"))
      (node (ref "U1") (pin "1") (pinfunction "VBAT_1") (pintype "power_in"))
    )
    (net (code "67") (name "VBAT") (class "Default")
      (node (ref "BAT_CONN") (pin "PWR") (pinfunction "PWR_PWR") (pintype "power_in"))
      (node (ref "Q1") (pin "3") (pinfunction "D_3") (pintype "passive"))
    )
    (net (code "68") (name "VBUS") (class "Default")
      (node (ref "D3") (pin "A") (pinfunction "A_A") (pintype "passive"))
      (node (ref "J1") (pin "1") (pinfunction "VBUS_1") (pintype "power_in"))
      (node (ref "Q1") (pin "1") (pinfunction "G_1") (pintype "passive"))
      (node (ref "R-MOS") (pin "2") (pinfunction "2_2") (pintype "passive"))
      (node (ref "VD1") (pin "5") (pinfunction "VBUS_5") (pintype "bidirectional"))
    )
    (net (code "69") (name "VREF+") (class "Default")
      (node (ref "C11") (pin "1") (pinfunction "1_1") (pintype "passive"))
      (node (ref "C12") (pin "1") (pinfunction "1_1") (pintype "passive"))
      (node (ref "FB1") (pin "2") (pinfunction "2_2") (pintype "passive"))
      (node (ref "U1") (pin "13") (pinfunction "VDDA/VREF+_13") (pintype "power_in"))
    )
    (net (code "70") (name "unconnected-(J1-ID-Pad4)") (class "Default")
      (node (ref "J1") (pin "4") (pinfunction "ID_4") (pintype "passive"))
    )
    (net (code "71") (name "unconnected-(J6-Pad1)") (class "Default")
      (node (ref "J6") (pin "1") (pinfunction "1_1") (pintype "passive"))
    )
    (net (code "72") (name "unconnected-(J6-Pad2)") (class "Default")
      (node (ref "J6") (pin "2") (pinfunction "2_2") (pintype "passive"))
    )
    (net (code "73") (name "unconnected-(J6-Pad8)") (class "Default")
      (node (ref "J6") (pin "8") (pinfunction "8_8") (pintype "passive"))
    )
    (net (code "74") (name "unconnected-(RST-SW-Pad2)") (class "Default")
      (node (ref "RST-SW") (pin "2") (pinfunction "2_2") (pintype "passive"))
    )
    (net (code "75") (name "unconnected-(RST-SW-Pad4)") (class "Default")
      (node (ref "RST-SW") (pin "4") (pinfunction "4_4") (pintype "passive"))
    )
    (net (code "76") (name "unconnected-(USR-SW-Pad2)") (class "Default")
      (node (ref "USR-SW") (pin "2") (pinfunction "2_2") (pintype "passive"))
    )
    (net (code "77") (name "unconnected-(USR-SW-Pad4)") (class "Default")
      (node (ref "USR-SW") (pin "4") (pinfunction "4_4") (pintype "passive"))
    )
  )
)
